# Sheet1-control.net
KiCad netlist of a schematic drawn in Altium Designer
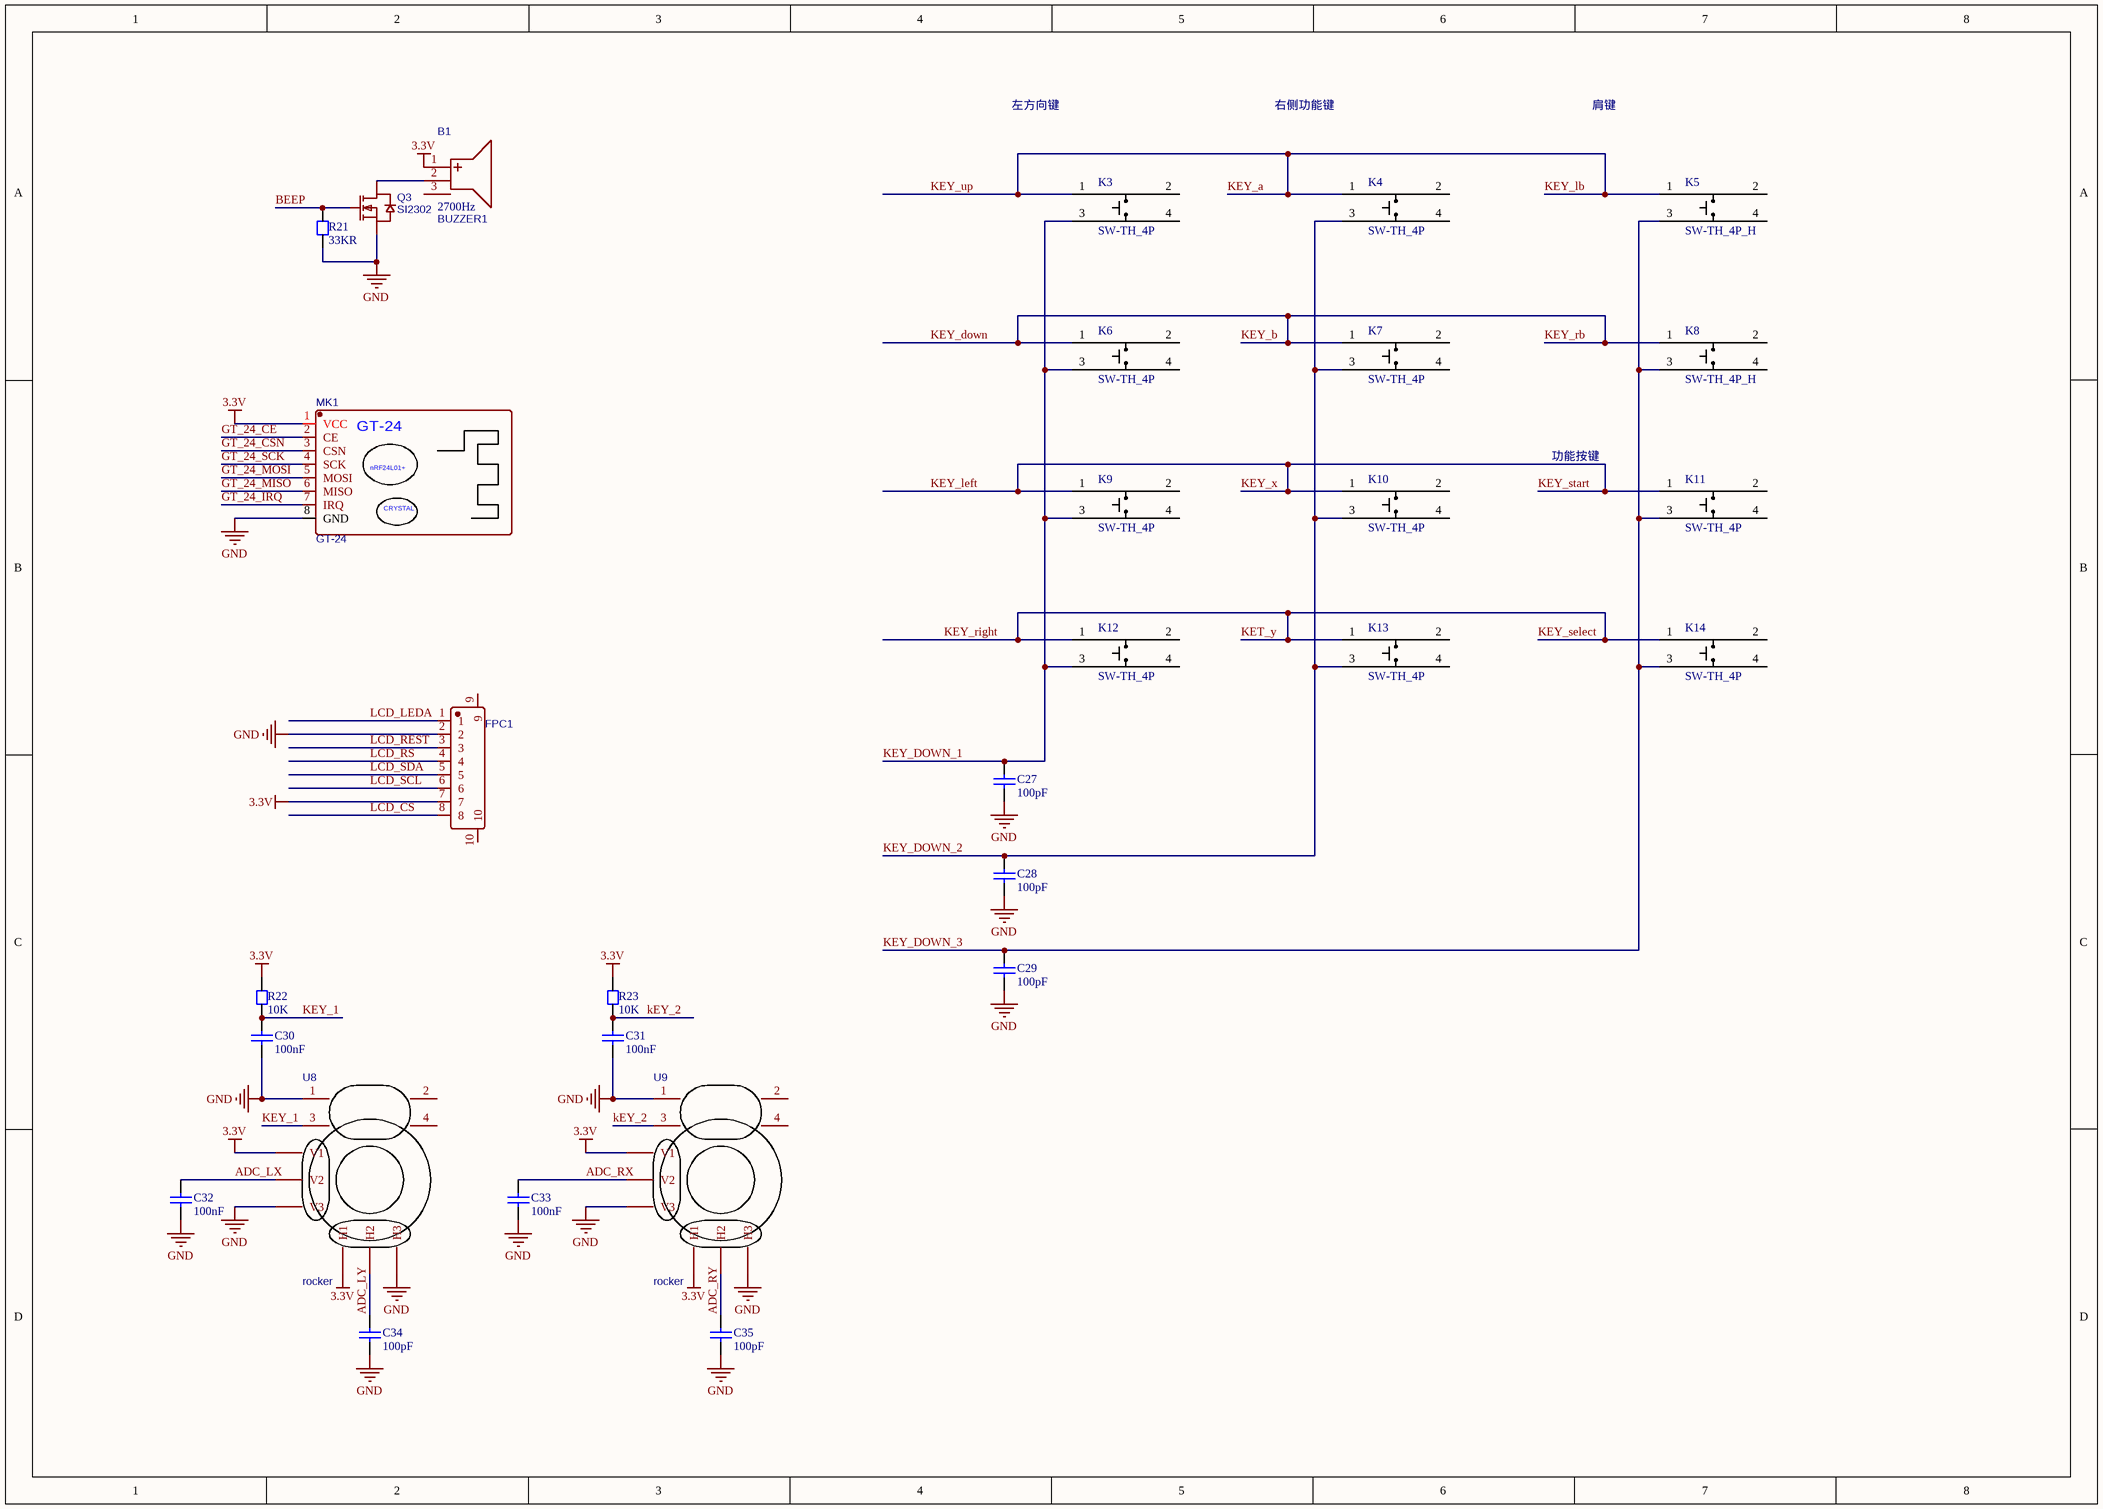
[diagram p0: Sheet1-control.SchDoc]

(export (version "E")
  (design (tool "Eeschema 10.0.6"))
  (components
    (comp (ref "B1")
      (value "BUZZER1")
      (footprint "BUZ-SMD_GSC7525RA")
      (description "2700Hz")
      (fields
        (field (name "MANUFACTURER") "INGHAi(赢海)")
        (field (name "MANUFACTURER PART") "GSC7525RA-16R2700")
        (field (name "CONTRIBUTOR") "LCSC")
      )
      (libsource (lib "base") (part "BUZZER1"))
    )
    (comp (ref "C27")
      (value "100pF")
      (footprint "CC1608-0603")
      (description "0603封装的电容")
      (fields (field (name "PUBLISHER") "Altium Limited"))
      (libsource (lib "base") (part "Cap Chip 0603"))
    )
    (comp (ref "C28")
      (value "100pF")
      (footprint "CC1608-0603")
      (description "0603封装的电容")
      (fields (field (name "PUBLISHER") "Altium Limited"))
      (libsource (lib "base") (part "Cap Chip 0603"))
    )
    (comp (ref "C29")
      (value "100pF")
      (footprint "CC1608-0603")
      (description "0603封装的电容")
      (fields (field (name "PUBLISHER") "Altium Limited"))
      (libsource (lib "base") (part "Cap Chip 0603"))
    )
    (comp (ref "C30")
      (value "100nF")
      (footprint "CC1608-0603")
      (description "0603封装的电容")
      (fields (field (name "PUBLISHER") "Altium Limited"))
      (libsource (lib "base") (part "Cap Chip 0603"))
    )
    (comp (ref "C31")
      (value "100nF")
      (footprint "CC1608-0603")
      (description "0603封装的电容")
      (fields (field (name "PUBLISHER") "Altium Limited"))
      (libsource (lib "base") (part "Cap Chip 0603"))
    )
    (comp (ref "C32")
      (value "100nF")
      (footprint "CC1608-0603")
      (description "0603封装的电容")
      (fields (field (name "PUBLISHER") "Altium Limited"))
      (libsource (lib "base") (part "Cap Chip 0603"))
    )
    (comp (ref "C33")
      (value "100nF")
      (footprint "CC1608-0603")
      (description "0603封装的电容")
      (fields (field (name "PUBLISHER") "Altium Limited"))
      (libsource (lib "base") (part "Cap Chip 0603"))
    )
    (comp (ref "C34")
      (value "100pF")
      (footprint "CC1608-0603")
      (description "0603封装的电容")
      (fields (field (name "PUBLISHER") "Altium Limited"))
      (libsource (lib "base") (part "Cap Chip 0603"))
    )
    (comp (ref "C35")
      (value "100pF")
      (footprint "CC1608-0603")
      (description "0603封装的电容")
      (fields (field (name "PUBLISHER") "Altium Limited"))
      (libsource (lib "base") (part "Cap Chip 0603"))
    )
    (comp (ref "FPC1")
      (value "FFC 05 8P")
      (footprint "FFC-SMD_8P-P0.50")
      (fields
        (field (name "MANUFACTURER") "TXGA(特思嘉)")
        (field (name "MANUFACTURER PART") "FFC05001-08SBB124W5M-H")
        (field (name "CONTRIBUTOR") "LCSC")
      )
      (libsource (lib "Connectors") (part "FFC 05 8P"))
    )
    (comp (ref "K3")
      (value "SW-TH_4P")
      (footprint "SW-TH_4P")
      (description "轻触开关")
      (libsource (lib "base") (part "SW-TH_4P"))
    )
    (comp (ref "K4")
      (value "SW-TH_4P")
      (footprint "SW-TH_4P")
      (description "轻触开关")
      (libsource (lib "base") (part "SW-TH_4P"))
    )
    (comp (ref "K5")
      (value "SW-TH_4P_H")
      (footprint "SW-TH_KH-6X6X7H-ZJ")
      (description "卧式轻触开关")
      (libsource (lib "base") (part "SW-TH_4P_H"))
    )
    (comp (ref "K6")
      (value "SW-TH_4P")
      (footprint "SW-TH_4P")
      (description "轻触开关")
      (libsource (lib "base") (part "SW-TH_4P"))
    )
    (comp (ref "K7")
      (value "SW-TH_4P")
      (footprint "SW-TH_4P")
      (description "轻触开关")
      (libsource (lib "base") (part "SW-TH_4P"))
    )
    (comp (ref "K8")
      (value "SW-TH_4P_H")
      (footprint "SW-TH_KH-6X6X7H-ZJ")
      (description "卧式轻触开关")
      (libsource (lib "base") (part "SW-TH_4P_H"))
    )
    (comp (ref "K9")
      (value "SW-TH_4P")
      (footprint "SW-TH_4P")
      (description "轻触开关")
      (libsource (lib "base") (part "SW-TH_4P"))
    )
    (comp (ref "K10")
      (value "SW-TH_4P")
      (footprint "SW-TH_4P")
      (description "轻触开关")
      (libsource (lib "base") (part "SW-TH_4P"))
    )
    (comp (ref "K11")
      (value "SW-TH_4P")
      (footprint "SW-TH_4P")
      (description "轻触开关")
      (libsource (lib "base") (part "SW-TH_4P"))
    )
    (comp (ref "K12")
      (value "SW-TH_4P")
      (footprint "SW-TH_4P")
      (description "轻触开关")
      (libsource (lib "base") (part "SW-TH_4P"))
    )
    (comp (ref "K13")
      (value "SW-TH_4P")
      (footprint "SW-TH_4P")
      (description "轻触开关")
      (libsource (lib "base") (part "SW-TH_4P"))
    )
    (comp (ref "K14")
      (value "SW-TH_4P")
      (footprint "SW-TH_4P")
      (description "轻触开关")
      (libsource (lib "base") (part "SW-TH_4P"))
    )
    (comp (ref "MK1")
      (value "GT-24")
      (footprint "WIRELM-SMD_AS01-ML01S")
      (description "工业级GT-24数传无线模块 2.4G NRF24L01&PA+LNA")
      (fields (field (name "MANUFACTURER") "Ashining(泽耀科技)") (field (name "MANUFACTURER PART") "AS01-ML01S"))
      (libsource (lib "sensor") (part "GT-24"))
    )
    (comp (ref "Q3")
      (value "SI2302")
      (footprint "SOT-23")
      (fields
        (field (name "MANUFACTURER") "TWGMC(台湾迪嘉)")
        (field (name "MANUFACTURER PART") "SI2306")
        (field (name "CONTRIBUTOR") "LCSC")
      )
      (libsource (lib "transistor") (part "SI2302"))
    )
    (comp (ref "R21")
      (value "33KR")
      (footprint "CR1608-0603")
      (description "贴片电阻")
      (libsource (lib "tianxiaohua_Schlib") (part "Chip resistor"))
    )
    (comp (ref "R22")
      (value "10K")
      (footprint "CR1608-0603")
      (description "0603封装电阻")
      (fields (field (name "PUBLISHER") "Altium Limited"))
      (libsource (lib "base") (part "Resistor Chip 0603"))
    )
    (comp (ref "R23")
      (value "10K")
      (footprint "CR1608-0603")
      (description "0603封装电阻")
      (fields (field (name "PUBLISHER") "Altium Limited"))
      (libsource (lib "base") (part "Resistor Chip 0603"))
    )
    (comp (ref "U8")
      (value "rocker")
      (footprint "PCBComponent_1")
      (fields (field (name "MANUFACTURER PART") "摇杆") (field (name "CONTRIBUTOR") "Alex_Ai"))
      (libsource (lib "base") (part "rocker"))
    )
    (comp (ref "U9")
      (value "rocker")
      (footprint "PCBComponent_1")
      (fields (field (name "MANUFACTURER PART") "摇杆") (field (name "CONTRIBUTOR") "Alex_Ai"))
      (libsource (lib "base") (part "rocker"))
    )
  )
  (nets
    (net (code "1") (name "/ADC_LX") (class "Default")
      (node (ref "C32") (pin "2") (pinfunction "2_2") (pintype "passive"))
      (node (ref "U8") (pin "6") (pinfunction "V2_6") (pintype "passive"))
    )
    (net (code "2") (name "/ADC_LY") (class "Default")
      (node (ref "C34") (pin "2") (pinfunction "2_2") (pintype "passive"))
      (node (ref "U8") (pin "9") (pinfunction "H2_9") (pintype "passive"))
    )
    (net (code "3") (name "/ADC_RX") (class "Default")
      (node (ref "C33") (pin "2") (pinfunction "2_2") (pintype "passive"))
      (node (ref "U9") (pin "6") (pinfunction "V2_6") (pintype "passive"))
    )
    (net (code "4") (name "/ADC_RY") (class "Default")
      (node (ref "C35") (pin "2") (pinfunction "2_2") (pintype "passive"))
      (node (ref "U9") (pin "9") (pinfunction "H2_9") (pintype "passive"))
    )
    (net (code "5") (name "/BEEP") (class "Default")
      (node (ref "Q3") (pin "1") (pinfunction "G_1") (pintype "passive"))
      (node (ref "R21") (pin "1") (pinfunction "1_1") (pintype "passive"))
    )
    (net (code "6") (name "/GT_24_CE") (class "Default")
      (node (ref "MK1") (pin "2") (pinfunction "CE_2") (pintype "passive"))
    )
    (net (code "7") (name "/GT_24_CSN") (class "Default")
      (node (ref "MK1") (pin "3") (pinfunction "CSN_3") (pintype "passive"))
    )
    (net (code "8") (name "/GT_24_IRQ") (class "Default")
      (node (ref "MK1") (pin "7") (pinfunction "IRQ_7") (pintype "passive"))
    )
    (net (code "9") (name "/GT_24_MISO") (class "Default")
      (node (ref "MK1") (pin "6") (pinfunction "MISO_6") (pintype "passive"))
    )
    (net (code "10") (name "/GT_24_MOSI") (class "Default")
      (node (ref "MK1") (pin "5") (pinfunction "MOSI_5") (pintype "passive"))
    )
    (net (code "11") (name "/GT_24_SCK") (class "Default")
      (node (ref "MK1") (pin "4") (pinfunction "SCK_4") (pintype "passive"))
    )
    (net (code "12") (name "/KET_y") (class "Default")
      (node (ref "K12") (pin "1") (pinfunction "1_1") (pintype "passive"))
      (node (ref "K13") (pin "1") (pinfunction "1_1") (pintype "passive"))
      (node (ref "K14") (pin "1") (pinfunction "1_1") (pintype "passive"))
    )
    (net (code "13") (name "/KEY_1") (class "Default")
      (node (ref "C30") (pin "2") (pinfunction "2_2") (pintype "passive"))
      (node (ref "R22") (pin "1") (pinfunction "1_1") (pintype "passive"))
      (node (ref "U8") (pin "3") (pinfunction "3_3") (pintype "passive"))
    )
    (net (code "14") (name "/KEY_DOWN_1") (class "Default")
      (node (ref "C27") (pin "2") (pinfunction "2_2") (pintype "passive"))
      (node (ref "K12") (pin "3") (pinfunction "3_3") (pintype "passive"))
      (node (ref "K3") (pin "3") (pinfunction "3_3") (pintype "passive"))
      (node (ref "K6") (pin "3") (pinfunction "3_3") (pintype "passive"))
      (node (ref "K9") (pin "3") (pinfunction "3_3") (pintype "passive"))
    )
    (net (code "15") (name "/KEY_DOWN_2") (class "Default")
      (node (ref "C28") (pin "2") (pinfunction "2_2") (pintype "passive"))
      (node (ref "K10") (pin "3") (pinfunction "3_3") (pintype "passive"))
      (node (ref "K13") (pin "3") (pinfunction "3_3") (pintype "passive"))
      (node (ref "K4") (pin "3") (pinfunction "3_3") (pintype "passive"))
      (node (ref "K7") (pin "3") (pinfunction "3_3") (pintype "passive"))
    )
    (net (code "16") (name "/KEY_DOWN_3") (class "Default")
      (node (ref "C29") (pin "2") (pinfunction "2_2") (pintype "passive"))
      (node (ref "K11") (pin "3") (pinfunction "3_3") (pintype "passive"))
      (node (ref "K14") (pin "3") (pinfunction "3_3") (pintype "passive"))
      (node (ref "K5") (pin "3") (pinfunction "3_3") (pintype "passive"))
      (node (ref "K8") (pin "3") (pinfunction "3_3") (pintype "passive"))
    )
    (net (code "17") (name "/KEY_a") (class "Default")
      (node (ref "K3") (pin "1") (pinfunction "1_1") (pintype "passive"))
      (node (ref "K4") (pin "1") (pinfunction "1_1") (pintype "passive"))
      (node (ref "K5") (pin "1") (pinfunction "1_1") (pintype "passive"))
    )
    (net (code "18") (name "/KEY_b") (class "Default")
      (node (ref "K6") (pin "1") (pinfunction "1_1") (pintype "passive"))
      (node (ref "K7") (pin "1") (pinfunction "1_1") (pintype "passive"))
      (node (ref "K8") (pin "1") (pinfunction "1_1") (pintype "passive"))
    )
    (net (code "19") (name "/KEY_left") (class "Default")
      (node (ref "K10") (pin "1") (pinfunction "1_1") (pintype "passive"))
      (node (ref "K11") (pin "1") (pinfunction "1_1") (pintype "passive"))
      (node (ref "K9") (pin "1") (pinfunction "1_1") (pintype "passive"))
    )
    (net (code "20") (name "/LCD_CS") (class "Default")
      (node (ref "FPC1") (pin "8") (pinfunction "8_8") (pintype "passive"))
    )
    (net (code "21") (name "/LCD_LEDA") (class "Default")
      (node (ref "FPC1") (pin "1") (pinfunction "1_1") (pintype "passive"))
    )
    (net (code "22") (name "/LCD_REST") (class "Default")
      (node (ref "FPC1") (pin "3") (pinfunction "3_3") (pintype "passive"))
    )
    (net (code "23") (name "/LCD_RS") (class "Default")
      (node (ref "FPC1") (pin "4") (pinfunction "4_4") (pintype "passive"))
    )
    (net (code "24") (name "/LCD_SCL") (class "Default")
      (node (ref "FPC1") (pin "6") (pinfunction "6_6") (pintype "passive"))
    )
    (net (code "25") (name "/LCD_SDA") (class "Default")
      (node (ref "FPC1") (pin "5") (pinfunction "5_5") (pintype "passive"))
    )
    (net (code "26") (name "/kEY_2") (class "Default")
      (node (ref "C31") (pin "2") (pinfunction "2_2") (pintype "passive"))
      (node (ref "R23") (pin "1") (pinfunction "1_1") (pintype "passive"))
      (node (ref "U9") (pin "3") (pinfunction "3_3") (pintype "passive"))
    )
    (net (code "27") (name "3.3V") (class "Default")
      (node (ref "B1") (pin "1") (pinfunction "+_1") (pintype "passive"))
      (node (ref "FPC1") (pin "7") (pinfunction "7_7") (pintype "passive"))
      (node (ref "MK1") (pin "1") (pinfunction "VCC_1") (pintype "passive"))
      (node (ref "R22") (pin "2") (pinfunction "2_2") (pintype "passive"))
      (node (ref "R23") (pin "2") (pinfunction "2_2") (pintype "passive"))
      (node (ref "U8") (pin "5") (pinfunction "V1_5") (pintype "passive"))
      (node (ref "U8") (pin "8") (pinfunction "H1_8") (pintype "passive"))
      (node (ref "U9") (pin "5") (pinfunction "V1_5") (pintype "passive"))
      (node (ref "U9") (pin "8") (pinfunction "H1_8") (pintype "passive"))
    )
    (net (code "28") (name "GND") (class "Default")
      (node (ref "C27") (pin "1") (pinfunction "1_1") (pintype "passive"))
      (node (ref "C28") (pin "1") (pinfunction "1_1") (pintype "passive"))
      (node (ref "C29") (pin "1") (pinfunction "1_1") (pintype "passive"))
      (node (ref "C30") (pin "1") (pinfunction "1_1") (pintype "passive"))
      (node (ref "C31") (pin "1") (pinfunction "1_1") (pintype "passive"))
      (node (ref "C32") (pin "1") (pinfunction "1_1") (pintype "passive"))
      (node (ref "C33") (pin "1") (pinfunction "1_1") (pintype "passive"))
      (node (ref "C34") (pin "1") (pinfunction "1_1") (pintype "passive"))
      (node (ref "C35") (pin "1") (pinfunction "1_1") (pintype "passive"))
      (node (ref "FPC1") (pin "2") (pinfunction "2_2") (pintype "passive"))
      (node (ref "MK1") (pin "8") (pinfunction "GND_8") (pintype "passive"))
      (node (ref "Q3") (pin "2") (pinfunction "S_2") (pintype "passive"))
      (node (ref "R21") (pin "2") (pinfunction "2_2") (pintype "passive"))
      (node (ref "U8") (pin "1") (pinfunction "1_1") (pintype "passive"))
      (node (ref "U8") (pin "10") (pinfunction "H3_10") (pintype "passive"))
      (node (ref "U8") (pin "7") (pinfunction "V3_7") (pintype "passive"))
      (node (ref "U9") (pin "1") (pinfunction "1_1") (pintype "passive"))
      (node (ref "U9") (pin "10") (pinfunction "H3_10") (pintype "passive"))
      (node (ref "U9") (pin "7") (pinfunction "V3_7") (pintype "passive"))
    )
    (net (code "29") (name "Net-(B1--)") (class "Default")
      (node (ref "B1") (pin "2") (pinfunction "-_2") (pintype "passive"))
      (node (ref "Q3") (pin "3") (pinfunction "D_3") (pintype "passive"))
    )
    (net (code "30") (name "unconnected-(B1-EH-Pad3)") (class "Default")
      (node (ref "B1") (pin "3") (pinfunction "EH_3") (pintype "passive"))
    )
    (net (code "31") (name "unconnected-(FPC1-Pad9)") (class "Default")
      (node (ref "FPC1") (pin "9") (pinfunction "9_9") (pintype "passive"))
    )
    (net (code "32") (name "unconnected-(FPC1-Pad10)") (class "Default")
      (node (ref "FPC1") (pin "10") (pinfunction "10_10") (pintype "passive"))
    )
    (net (code "33") (name "unconnected-(K3-Pad2)") (class "Default")
      (node (ref "K3") (pin "2") (pinfunction "2_2") (pintype "passive"))
    )
    (net (code "34") (name "unconnected-(K3-Pad4)") (class "Default")
      (node (ref "K3") (pin "4") (pinfunction "4_4") (pintype "passive"))
    )
    (net (code "35") (name "unconnected-(K4-Pad2)") (class "Default")
      (node (ref "K4") (pin "2") (pinfunction "2_2") (pintype "passive"))
    )
    (net (code "36") (name "unconnected-(K4-Pad4)") (class "Default")
      (node (ref "K4") (pin "4") (pinfunction "4_4") (pintype "passive"))
    )
    (net (code "37") (name "unconnected-(K5-Pad2)") (class "Default")
      (node (ref "K5") (pin "2") (pinfunction "2_2") (pintype "passive"))
    )
    (net (code "38") (name "unconnected-(K5-Pad4)") (class "Default")
      (node (ref "K5") (pin "4") (pinfunction "4_4") (pintype "passive"))
    )
    (net (code "39") (name "unconnected-(K6-Pad2)") (class "Default")
      (node (ref "K6") (pin "2") (pinfunction "2_2") (pintype "passive"))
    )
    (net (code "40") (name "unconnected-(K6-Pad4)") (class "Default")
      (node (ref "K6") (pin "4") (pinfunction "4_4") (pintype "passive"))
    )
    (net (code "41") (name "unconnected-(K7-Pad2)") (class "Default")
      (node (ref "K7") (pin "2") (pinfunction "2_2") (pintype "passive"))
    )
    (net (code "42") (name "unconnected-(K7-Pad4)") (class "Default")
      (node (ref "K7") (pin "4") (pinfunction "4_4") (pintype "passive"))
    )
    (net (code "43") (name "unconnected-(K8-Pad2)") (class "Default")
      (node (ref "K8") (pin "2") (pinfunction "2_2") (pintype "passive"))
    )
    (net (code "44") (name "unconnected-(K8-Pad4)") (class "Default")
      (node (ref "K8") (pin "4") (pinfunction "4_4") (pintype "passive"))
    )
    (net (code "45") (name "unconnected-(K9-Pad2)") (class "Default")
      (node (ref "K9") (pin "2") (pinfunction "2_2") (pintype "passive"))
    )
    (net (code "46") (name "unconnected-(K9-Pad4)") (class "Default")
      (node (ref "K9") (pin "4") (pinfunction "4_4") (pintype "passive"))
    )
    (net (code "47") (name "unconnected-(K10-Pad2)") (class "Default")
      (node (ref "K10") (pin "2") (pinfunction "2_2") (pintype "passive"))
    )
    (net (code "48") (name "unconnected-(K10-Pad4)") (class "Default")
      (node (ref "K10") (pin "4") (pinfunction "4_4") (pintype "passive"))
    )
    (net (code "49") (name "unconnected-(K11-Pad2)") (class "Default")
      (node (ref "K11") (pin "2") (pinfunction "2_2") (pintype "passive"))
    )
    (net (code "50") (name "unconnected-(K11-Pad4)") (class "Default")
      (node (ref "K11") (pin "4") (pinfunction "4_4") (pintype "passive"))
    )
    (net (code "51") (name "unconnected-(K12-Pad2)") (class "Default")
      (node (ref "K12") (pin "2") (pinfunction "2_2") (pintype "passive"))
    )
    (net (code "52") (name "unconnected-(K12-Pad4)") (class "Default")
      (node (ref "K12") (pin "4") (pinfunction "4_4") (pintype "passive"))
    )
    (net (code "53") (name "unconnected-(K13-Pad2)") (class "Default")
      (node (ref "K13") (pin "2") (pinfunction "2_2") (pintype "passive"))
    )
    (net (code "54") (name "unconnected-(K13-Pad4)") (class "Default")
      (node (ref "K13") (pin "4") (pinfunction "4_4") (pintype "passive"))
    )
    (net (code "55") (name "unconnected-(K14-Pad2)") (class "Default")
      (node (ref "K14") (pin "2") (pinfunction "2_2") (pintype "passive"))
    )
    (net (code "56") (name "unconnected-(K14-Pad4)") (class "Default")
      (node (ref "K14") (pin "4") (pinfunction "4_4") (pintype "passive"))
    )
    (net (code "57") (name "unconnected-(U8-Pad2)") (class "Default")
      (node (ref "U8") (pin "2") (pinfunction "2_2") (pintype "passive"))
    )
    (net (code "58") (name "unconnected-(U8-Pad4)") (class "Default")
      (node (ref "U8") (pin "4") (pinfunction "4_4") (pintype "passive"))
    )
    (net (code "59") (name "unconnected-(U9-Pad2)") (class "Default")
      (node (ref "U9") (pin "2") (pinfunction "2_2") (pintype "passive"))
    )
    (net (code "60") (name "unconnected-(U9-Pad4)") (class "Default")
      (node (ref "U9") (pin "4") (pinfunction "4_4") (pintype "passive"))
    )
  )
)
